# ProgrammatorBoard.net
KiCad netlist of a schematic drawn in Altium Designer
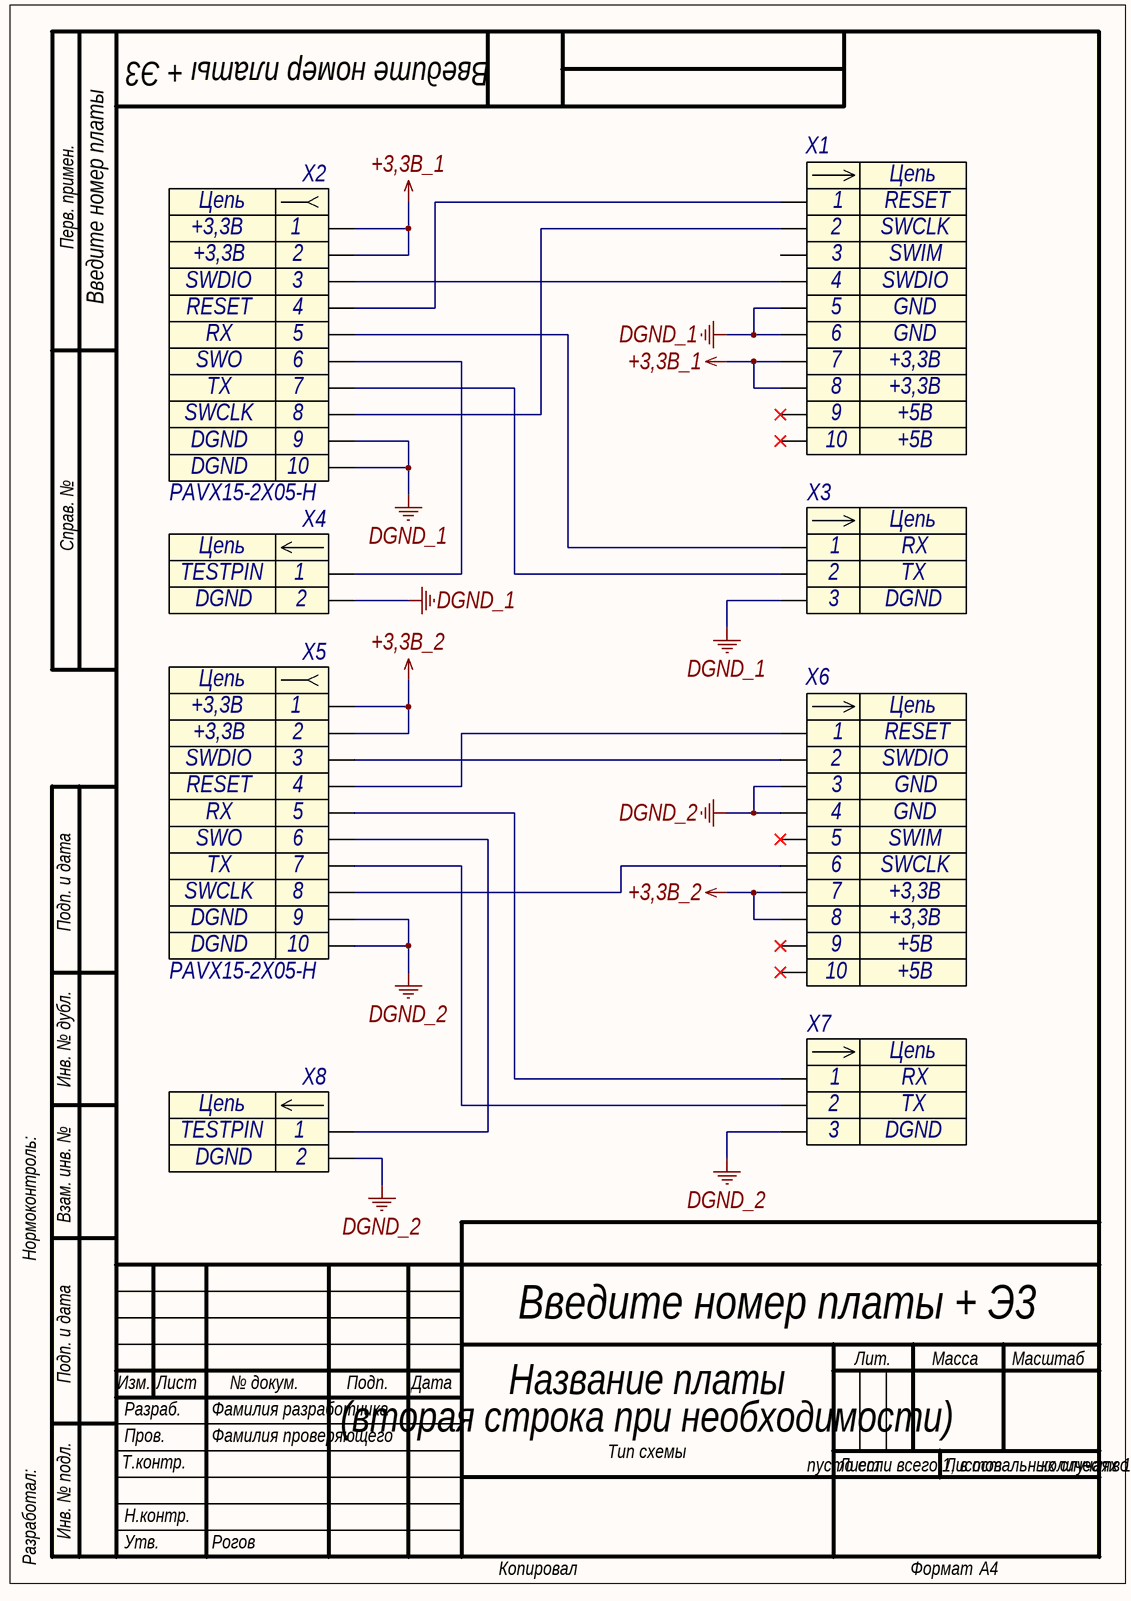
[diagram p0: ProgrammatorBoard.SchDoc]

(export (version "E")
  (design (tool "Eeschema 10.0.6"))
  (components
    (comp (ref "X1")
      (value "Header_10_plg")
      (footprint "IDC-10MS")
      (description "Разъем - 10 конт. вилка")
      (fields (field (name "PART NUMBER") "DS1013-10SSiB1-B-0"))
      (libsource (lib "MOP44") (part "Header_10_plg"))
    )
    (comp (ref "X2")
      (value "Header_10_sct")
      (footprint "PAVX15-2X05-H")
      (description "Разъем - 10 конт. розетка")
      (fields (field (name "PART NUMBER") "PAVX15-2X05-H"))
      (libsource (lib "MOP44") (part "Header_10_sct"))
    )
    (comp (ref "X3")
      (value "Header_3_plg")
      (footprint "PLS-3")
      (description "Разъем - 3 конт. вилка")
      (fields (field (name "PART NUMBER") "DS1021-1*3SF112-B"))
      (libsource (lib "MOP44") (part "Header_3_plg"))
    )
    (comp (ref "X4")
      (value "~")
      (footprint "PLS-2")
      (description "Разъем - 2 конт. вилка")
      (libsource (lib "MOP44") (part "Header_2_plg"))
    )
    (comp (ref "X5")
      (value "Header_10_sct")
      (footprint "PAVX15-2X05-H")
      (description "Разъем - 10 конт. розетка")
      (fields (field (name "PART NUMBER") "PAVX15-2X05-H"))
      (libsource (lib "MOP44") (part "Header_10_sct"))
    )
    (comp (ref "X6")
      (value "Header_10_plg")
      (footprint "IDC-10MS")
      (description "Разъем - 10 конт. вилка")
      (fields (field (name "PART NUMBER") "DS1013-10SSiB1-B-0"))
      (libsource (lib "MOP44") (part "Header_10_plg"))
    )
    (comp (ref "X7")
      (value "Header_3_plg")
      (footprint "PLS-3")
      (description "Разъем - 3 конт. вилка")
      (fields (field (name "PART NUMBER") "DS1021-1*3SF112-B"))
      (libsource (lib "MOP44") (part "Header_3_plg"))
    )
    (comp (ref "X8")
      (value "~")
      (footprint "PLS-2")
      (description "Разъем - 2 конт. вилка")
      (libsource (lib "MOP44") (part "Header_2_plg"))
    )
  )
  (nets
    (net (code "1") (name "+3,3B_1") (class "Default")
      (node (ref "X1") (pin "7") (pinfunction "7_7") (pintype "passive"))
      (node (ref "X1") (pin "8") (pinfunction "8_8") (pintype "passive"))
      (node (ref "X2") (pin "1") (pinfunction "1_1") (pintype "passive"))
      (node (ref "X2") (pin "2") (pinfunction "2_2") (pintype "passive"))
    )
    (net (code "2") (name "+3,3B_2") (class "Default")
      (node (ref "X5") (pin "1") (pinfunction "1_1") (pintype "passive"))
      (node (ref "X5") (pin "2") (pinfunction "2_2") (pintype "passive"))
      (node (ref "X6") (pin "7") (pinfunction "7_7") (pintype "passive"))
      (node (ref "X6") (pin "8") (pinfunction "8_8") (pintype "passive"))
    )
    (net (code "3") (name "DGND_1") (class "Default")
      (node (ref "X1") (pin "5") (pinfunction "5_5") (pintype "passive"))
      (node (ref "X1") (pin "6") (pinfunction "6_6") (pintype "passive"))
      (node (ref "X2") (pin "10") (pinfunction "10_10") (pintype "passive"))
      (node (ref "X2") (pin "9") (pinfunction "9_9") (pintype "passive"))
      (node (ref "X3") (pin "3") (pinfunction "3_3") (pintype "passive"))
      (node (ref "X4") (pin "2") (pinfunction "2_2") (pintype "passive"))
    )
    (net (code "4") (name "DGND_2") (class "Default")
      (node (ref "X5") (pin "10") (pinfunction "10_10") (pintype "passive"))
      (node (ref "X5") (pin "9") (pinfunction "9_9") (pintype "passive"))
      (node (ref "X6") (pin "3") (pinfunction "3_3") (pintype "passive"))
      (node (ref "X6") (pin "4") (pinfunction "4_4") (pintype "passive"))
      (node (ref "X7") (pin "3") (pinfunction "3_3") (pintype "passive"))
      (node (ref "X8") (pin "2") (pinfunction "2_2") (pintype "passive"))
    )
    (net (code "5") (name "Net-(X1-Pad1)") (class "Default")
      (node (ref "X1") (pin "1") (pinfunction "1_1") (pintype "passive"))
      (node (ref "X2") (pin "4") (pinfunction "4_4") (pintype "passive"))
    )
    (net (code "6") (name "Net-(X1-Pad2)") (class "Default")
      (node (ref "X1") (pin "2") (pinfunction "2_2") (pintype "passive"))
      (node (ref "X2") (pin "8") (pinfunction "8_8") (pintype "passive"))
    )
    (net (code "7") (name "Net-(X1-Pad4)") (class "Default")
      (node (ref "X1") (pin "4") (pinfunction "4_4") (pintype "passive"))
      (node (ref "X2") (pin "3") (pinfunction "3_3") (pintype "passive"))
    )
    (net (code "8") (name "Net-(X2-Pad5)") (class "Default")
      (node (ref "X2") (pin "5") (pinfunction "5_5") (pintype "passive"))
      (node (ref "X3") (pin "1") (pinfunction "1_1") (pintype "passive"))
    )
    (net (code "9") (name "Net-(X2-Pad6)") (class "Default")
      (node (ref "X2") (pin "6") (pinfunction "6_6") (pintype "passive"))
      (node (ref "X4") (pin "1") (pinfunction "1_1") (pintype "passive"))
    )
    (net (code "10") (name "Net-(X2-Pad7)") (class "Default")
      (node (ref "X2") (pin "7") (pinfunction "7_7") (pintype "passive"))
      (node (ref "X3") (pin "2") (pinfunction "2_2") (pintype "passive"))
    )
    (net (code "11") (name "Net-(X5-Pad3)") (class "Default")
      (node (ref "X5") (pin "3") (pinfunction "3_3") (pintype "passive"))
      (node (ref "X6") (pin "2") (pinfunction "2_2") (pintype "passive"))
    )
    (net (code "12") (name "Net-(X5-Pad4)") (class "Default")
      (node (ref "X5") (pin "4") (pinfunction "4_4") (pintype "passive"))
      (node (ref "X6") (pin "1") (pinfunction "1_1") (pintype "passive"))
    )
    (net (code "13") (name "Net-(X5-Pad5)") (class "Default")
      (node (ref "X5") (pin "5") (pinfunction "5_5") (pintype "passive"))
      (node (ref "X7") (pin "1") (pinfunction "1_1") (pintype "passive"))
    )
    (net (code "14") (name "Net-(X5-Pad6)") (class "Default")
      (node (ref "X5") (pin "6") (pinfunction "6_6") (pintype "passive"))
      (node (ref "X8") (pin "1") (pinfunction "1_1") (pintype "passive"))
    )
    (net (code "15") (name "Net-(X5-Pad7)") (class "Default")
      (node (ref "X5") (pin "7") (pinfunction "7_7") (pintype "passive"))
      (node (ref "X7") (pin "2") (pinfunction "2_2") (pintype "passive"))
    )
    (net (code "16") (name "Net-(X5-Pad8)") (class "Default")
      (node (ref "X5") (pin "8") (pinfunction "8_8") (pintype "passive"))
      (node (ref "X6") (pin "6") (pinfunction "6_6") (pintype "passive"))
    )
    (net (code "17") (name "unconnected-(X1-Pad3)") (class "Default")
      (node (ref "X1") (pin "3") (pinfunction "3_3") (pintype "passive"))
    )
    (net (code "18") (name "unconnected-(X1-Pad9)") (class "Default")
      (node (ref "X1") (pin "9") (pinfunction "9_9") (pintype "passive+no_connect"))
    )
    (net (code "19") (name "unconnected-(X1-Pad10)") (class "Default")
      (node (ref "X1") (pin "10") (pinfunction "10_10") (pintype "passive+no_connect"))
    )
    (net (code "20") (name "unconnected-(X6-Pad5)") (class "Default")
      (node (ref "X6") (pin "5") (pinfunction "5_5") (pintype "passive+no_connect"))
    )
    (net (code "21") (name "unconnected-(X6-Pad9)") (class "Default")
      (node (ref "X6") (pin "9") (pinfunction "9_9") (pintype "passive+no_connect"))
    )
    (net (code "22") (name "unconnected-(X6-Pad10)") (class "Default")
      (node (ref "X6") (pin "10") (pinfunction "10_10") (pintype "passive+no_connect"))
    )
  )
)
